# iterasi3.net
KiCad netlist of a schematic drawn in EAGLE
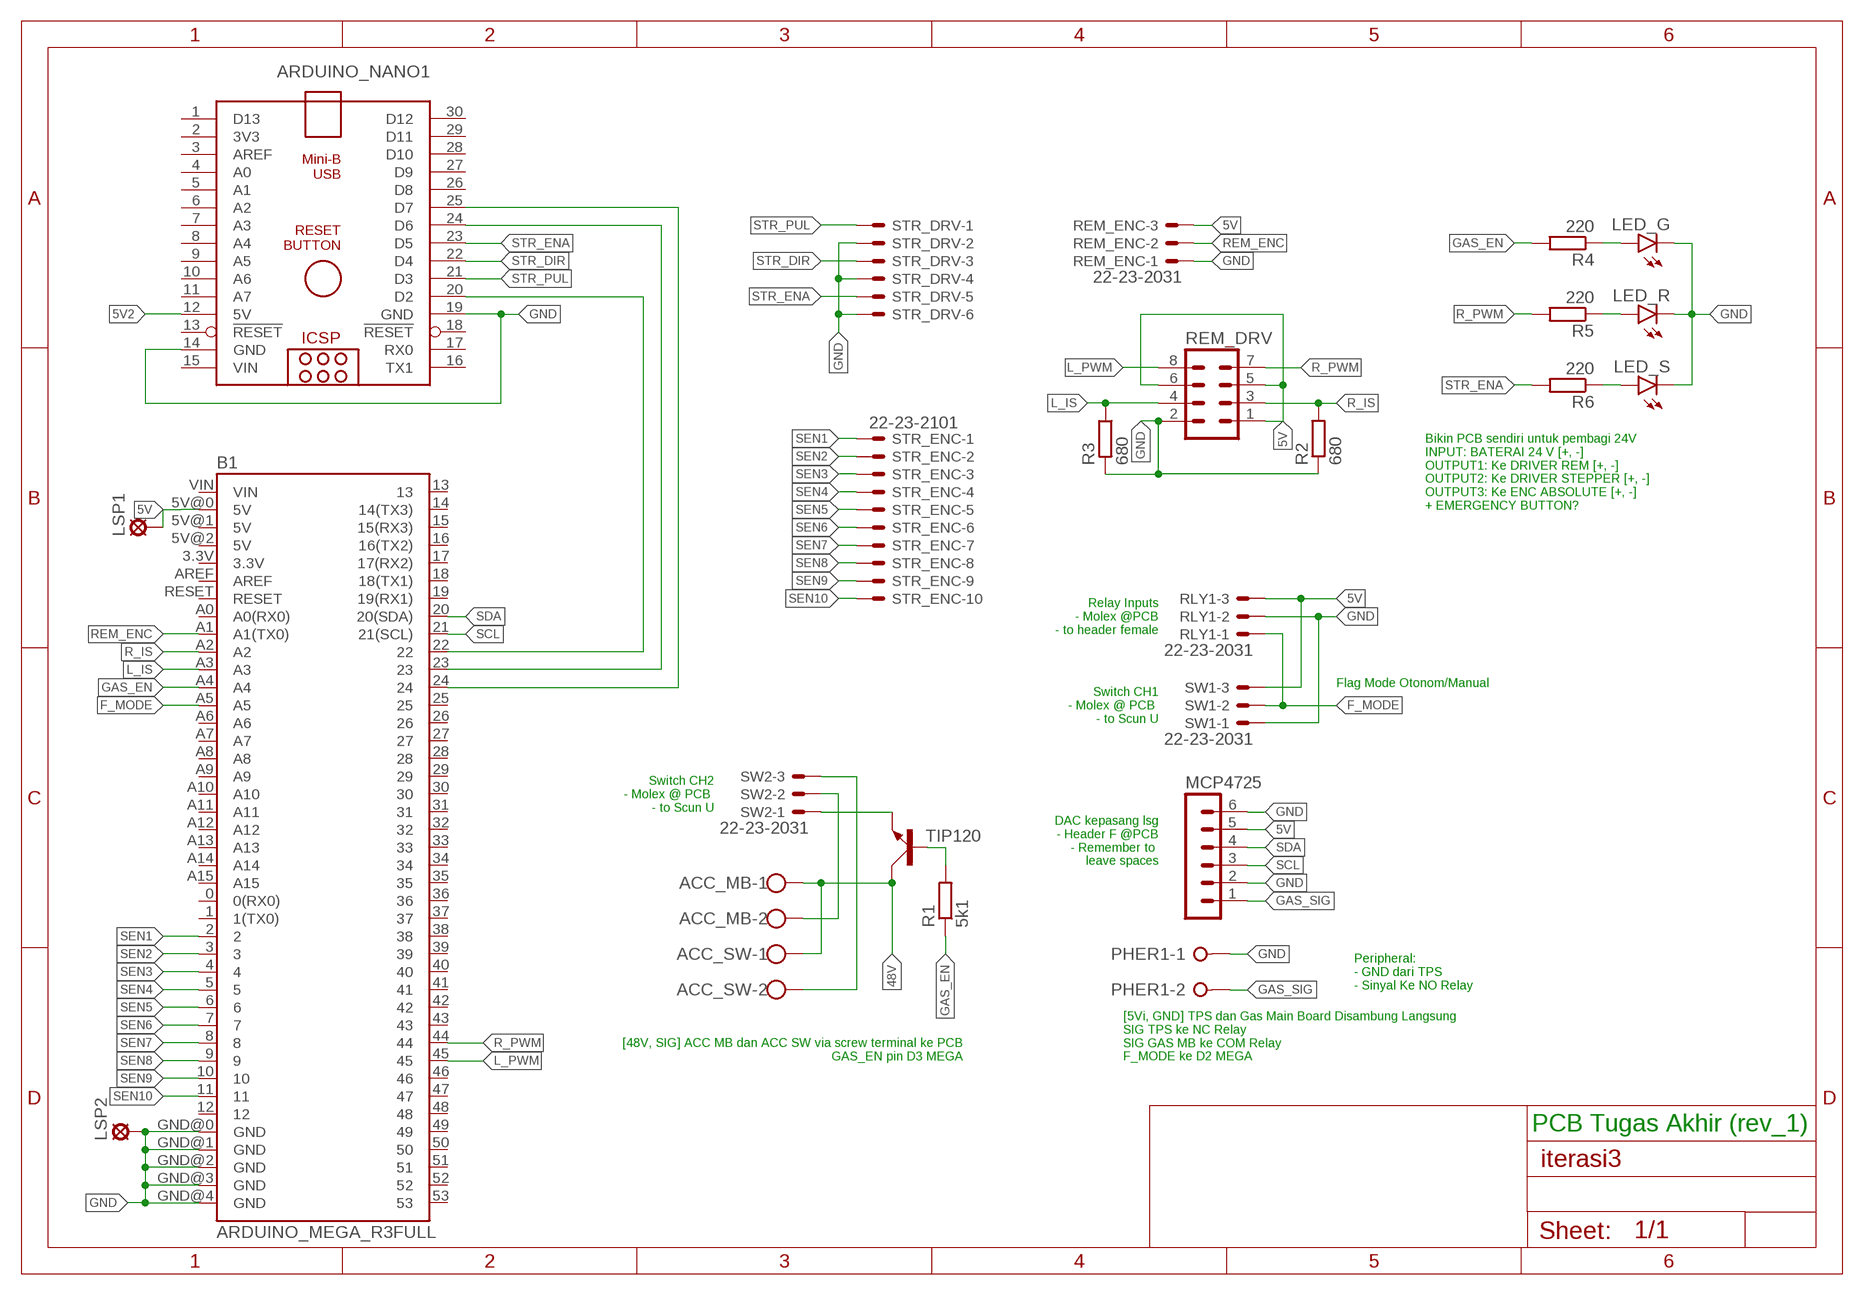
[diagram p0: schematic, sheet 1]

(export (version "E")
  (design (tool "Eeschema 10.0.6"))
  (components
    (comp (ref "ACC_MB")
      (value "W237-102")
      (footprint "eagle-import:W237-102")
      (fields (field (name "MPN") "237-102"))
      (libsource (lib "eagle-import") (part "W237-102"))
    )
    (comp (ref "ACC_SW")
      (value "W237-102")
      (footprint "eagle-import:W237-102")
      (fields (field (name "MPN") "237-102"))
      (libsource (lib "eagle-import") (part "W237-102"))
    )
    (comp (ref "ARDUINO_NANO1")
      (value "ARDUINO_NANO")
      (footprint "eagle-import:ARDUINO_NANO")
      (libsource (lib "eagle-import") (part "ARDUINO_NANO"))
    )
    (comp (ref "B1")
      (value "ARDUINO_MEGA_R3FULL")
      (footprint "eagle-import:ARDUINO_MEGA")
      (libsource (lib "eagle-import") (part "ARDUINO_MEGA_R3FULL"))
    )
    (comp (ref "LED_G")
      (value "TLLY4400")
      (footprint "eagle-import:LED3MM")
      (fields (field (name "MF") "VISHAY SEMICONDUCTOR"))
      (libsource (lib "eagle-import") (part "TLLY4400"))
    )
    (comp (ref "LED_R")
      (value "TLLY4400")
      (footprint "eagle-import:LED3MM")
      (fields (field (name "MF") "VISHAY SEMICONDUCTOR"))
      (libsource (lib "eagle-import") (part "TLLY4400"))
    )
    (comp (ref "LED_S")
      (value "TLLY4400")
      (footprint "eagle-import:LED3MM")
      (fields (field (name "MF") "VISHAY SEMICONDUCTOR"))
      (libsource (lib "eagle-import") (part "TLLY4400"))
    )
    (comp (ref "LSP1")
      (value "SE13")
      (footprint "eagle-import:SE13")
      (libsource (lib "eagle-import") (part "SE13"))
    )
    (comp (ref "LSP2")
      (value "SE13")
      (footprint "eagle-import:SE13")
      (libsource (lib "eagle-import") (part "SE13"))
    )
    (comp (ref "MCP4725")
      (value "MA06-1")
      (footprint "eagle-import:MA06-1")
      (libsource (lib "eagle-import") (part "MA06-1"))
    )
    (comp (ref "PHER1")
      (value "GND_TPS/RELAY_NO")
      (footprint "eagle-import:W237-132")
      (libsource (lib "eagle-import") (part "W237-02P"))
    )
    (comp (ref "R1")
      (value "5k1")
      (footprint "eagle-import:0207_10")
      (libsource (lib "eagle-import") (part "R-EU_0207/10"))
    )
    (comp (ref "R2")
      (value "680")
      (footprint "eagle-import:0207_10")
      (libsource (lib "eagle-import") (part "R-EU_0207/10"))
    )
    (comp (ref "R3")
      (value "680")
      (footprint "eagle-import:0207_10")
      (libsource (lib "eagle-import") (part "R-EU_0207/10"))
    )
    (comp (ref "R4")
      (value "220")
      (footprint "eagle-import:0207_10")
      (libsource (lib "eagle-import") (part "R-EU_0207/10"))
    )
    (comp (ref "R5")
      (value "220")
      (footprint "eagle-import:0207_10")
      (libsource (lib "eagle-import") (part "R-EU_0207/10"))
    )
    (comp (ref "R6")
      (value "220")
      (footprint "eagle-import:0207_10")
      (libsource (lib "eagle-import") (part "R-EU_0207/10"))
    )
    (comp (ref "REM_DRV")
      (value "MA04-2")
      (footprint "eagle-import:MA04-2")
      (libsource (lib "eagle-import") (part "MA04-2"))
    )
    (comp (ref "REM_ENC")
      (value "22-23-2031")
      (footprint "eagle-import:22-23-2031")
      (fields (field (name "MF") "MOLEX"))
      (libsource (lib "eagle-import") (part "22-23-2031"))
    )
    (comp (ref "RLY1")
      (value "22-23-2031")
      (footprint "eagle-import:22-23-2031")
      (fields (field (name "MF") "MOLEX"))
      (libsource (lib "eagle-import") (part "22-23-2031"))
    )
    (comp (ref "STR_DRV")
      (value "22-23-2061")
      (footprint "eagle-import:22-23-2061")
      (fields (field (name "MF") "MOLEX"))
      (libsource (lib "eagle-import") (part "22-23-2061"))
    )
    (comp (ref "STR_ENC")
      (value "22-23-2101")
      (footprint "eagle-import:22-23-2101")
      (fields (field (name "MF") "MOLEX"))
      (libsource (lib "eagle-import") (part "22-23-2101"))
    )
    (comp (ref "SW1")
      (value "22-23-2031")
      (footprint "eagle-import:22-23-2031")
      (fields (field (name "MF") "MOLEX"))
      (libsource (lib "eagle-import") (part "22-23-2031"))
    )
    (comp (ref "SW2")
      (value "22-23-2031")
      (footprint "eagle-import:22-23-2031")
      (fields (field (name "MF") "MOLEX"))
      (libsource (lib "eagle-import") (part "22-23-2031"))
    )
    (comp (ref "TIP120")
      (value "TIP41C")
      (footprint "eagle-import:TO220AV")
      (libsource (lib "eagle-import") (part "TIP41C"))
    )
  )
  (nets
    (net (code "1") (name "/VIN") (class "Default")
      (node (ref "ARDUINO_NANO1") (pin "15") (pinfunction "VIN_15") (pintype "power_in"))
    )
    (net (code "2") (name "5V") (class "Default")
      (node (ref "B1") (pin "5V@0") (pinfunction "5V_5V@0") (pintype "bidirectional"))
      (node (ref "LSP1") (pin "MP") (pinfunction "MP_MP") (pintype "passive"))
      (node (ref "MCP4725") (pin "5") (pinfunction "5_5") (pintype "passive"))
      (node (ref "REM_DRV") (pin "1") (pinfunction "1_1") (pintype "passive"))
      (node (ref "REM_DRV") (pin "5") (pinfunction "5_5") (pintype "passive"))
      (node (ref "REM_DRV") (pin "6") (pinfunction "6_6") (pintype "passive"))
      (node (ref "REM_ENC") (pin "3") (pinfunction "S_3") (pintype "passive"))
      (node (ref "RLY1") (pin "3") (pinfunction "S_3") (pintype "passive"))
      (node (ref "SW1") (pin "3") (pinfunction "S_3") (pintype "passive"))
    )
    (net (code "3") (name "5V2") (class "Default")
      (node (ref "ARDUINO_NANO1") (pin "12") (pinfunction "5V_12") (pintype "power_in"))
    )
    (net (code "4") (name "48V") (class "Default")
      (node (ref "ACC_MB") (pin "1") (pinfunction "KL_1") (pintype "passive"))
      (node (ref "ACC_SW") (pin "1") (pinfunction "KL_1") (pintype "passive"))
      (node (ref "TIP120") (pin "C") (pinfunction "C_C") (pintype "passive"))
    )
    (net (code "5") (name "F_MODE") (class "Default")
      (node (ref "B1") (pin "A5") (pinfunction "A5_A5") (pintype "bidirectional"))
      (node (ref "RLY1") (pin "1") (pinfunction "S_1") (pintype "passive"))
      (node (ref "SW1") (pin "2") (pinfunction "S_2") (pintype "passive"))
    )
    (net (code "6") (name "GAS_EN") (class "Default")
      (node (ref "B1") (pin "A4") (pinfunction "A4_A4") (pintype "bidirectional"))
      (node (ref "R1") (pin "1") (pinfunction "1_1") (pintype "passive"))
      (node (ref "R4") (pin "2") (pinfunction "2_2") (pintype "passive"))
    )
    (net (code "7") (name "GAS_SIG") (class "Default")
      (node (ref "MCP4725") (pin "1") (pinfunction "1_1") (pintype "passive"))
      (node (ref "PHER1") (pin "2") (pinfunction "KL_2") (pintype "passive"))
    )
    (net (code "8") (name "GND") (class "Default")
      (node (ref "ARDUINO_NANO1") (pin "14") (pinfunction "GND_14") (pintype "power_in"))
      (node (ref "ARDUINO_NANO1") (pin "19") (pinfunction "GND_19") (pintype "power_in"))
      (node (ref "B1") (pin "GND@0") (pinfunction "GND_GND@0") (pintype "bidirectional"))
      (node (ref "B1") (pin "GND@1") (pinfunction "GND_GND@1") (pintype "bidirectional"))
      (node (ref "B1") (pin "GND@2") (pinfunction "GND_GND@2") (pintype "bidirectional"))
      (node (ref "B1") (pin "GND@3") (pinfunction "GND_GND@3") (pintype "bidirectional"))
      (node (ref "B1") (pin "GND@4") (pinfunction "GND_GND@4") (pintype "bidirectional"))
      (node (ref "LED_G") (pin "K") (pinfunction "C_K") (pintype "passive"))
      (node (ref "LED_R") (pin "K") (pinfunction "C_K") (pintype "passive"))
      (node (ref "LED_S") (pin "K") (pinfunction "C_K") (pintype "passive"))
      (node (ref "LSP2") (pin "MP") (pinfunction "MP_MP") (pintype "passive"))
      (node (ref "MCP4725") (pin "2") (pinfunction "2_2") (pintype "passive"))
      (node (ref "MCP4725") (pin "6") (pinfunction "6_6") (pintype "passive"))
      (node (ref "PHER1") (pin "1") (pinfunction "KL_1") (pintype "passive"))
      (node (ref "R2") (pin "1") (pinfunction "1_1") (pintype "passive"))
      (node (ref "R3") (pin "2") (pinfunction "2_2") (pintype "passive"))
      (node (ref "REM_DRV") (pin "2") (pinfunction "2_2") (pintype "passive"))
      (node (ref "REM_ENC") (pin "1") (pinfunction "S_1") (pintype "passive"))
      (node (ref "RLY1") (pin "2") (pinfunction "S_2") (pintype "passive"))
      (node (ref "STR_DRV") (pin "2") (pinfunction "S_2") (pintype "passive"))
      (node (ref "STR_DRV") (pin "4") (pinfunction "S_4") (pintype "passive"))
      (node (ref "STR_DRV") (pin "6") (pinfunction "S_6") (pintype "passive"))
      (node (ref "SW1") (pin "1") (pinfunction "S_1") (pintype "passive"))
    )
    (net (code "9") (name "L_IS") (class "Default")
      (node (ref "B1") (pin "A3") (pinfunction "A3_A3") (pintype "bidirectional"))
      (node (ref "R3") (pin "1") (pinfunction "1_1") (pintype "passive"))
      (node (ref "REM_DRV") (pin "4") (pinfunction "4_4") (pintype "passive"))
    )
    (net (code "10") (name "L_PWM") (class "Default")
      (node (ref "B1") (pin "45") (pinfunction "45_45") (pintype "bidirectional"))
      (node (ref "REM_DRV") (pin "8") (pinfunction "8_8") (pintype "passive"))
    )
    (net (code "11") (name "Net-(ACC_MBB-KL)") (class "Default")
      (node (ref "ACC_MB") (pin "2") (pinfunction "KL_2") (pintype "passive"))
      (node (ref "SW2") (pin "2") (pinfunction "S_2") (pintype "passive"))
    )
    (net (code "12") (name "Net-(ACC_SWB-KL)") (class "Default")
      (node (ref "ACC_SW") (pin "2") (pinfunction "KL_2") (pintype "passive"))
      (node (ref "SW2") (pin "3") (pinfunction "S_3") (pintype "passive"))
    )
    (net (code "13") (name "Net-(ARDUINO_NANO1-D2)") (class "Default")
      (node (ref "ARDUINO_NANO1") (pin "20") (pinfunction "D2_20") (pintype "bidirectional"))
      (node (ref "B1") (pin "22") (pinfunction "22_22") (pintype "bidirectional"))
    )
    (net (code "14") (name "Net-(ARDUINO_NANO1-D6)") (class "Default")
      (node (ref "ARDUINO_NANO1") (pin "24") (pinfunction "D6_24") (pintype "bidirectional"))
      (node (ref "B1") (pin "23") (pinfunction "23_23") (pintype "bidirectional"))
    )
    (net (code "15") (name "Net-(ARDUINO_NANO1-D7)") (class "Default")
      (node (ref "ARDUINO_NANO1") (pin "25") (pinfunction "D7_25") (pintype "bidirectional"))
      (node (ref "B1") (pin "24") (pinfunction "24_24") (pintype "bidirectional"))
    )
    (net (code "16") (name "Net-(LED_G-PadA)") (class "Default")
      (node (ref "LED_G") (pin "A") (pinfunction "A_A") (pintype "passive"))
      (node (ref "R4") (pin "1") (pinfunction "1_1") (pintype "passive"))
    )
    (net (code "17") (name "Net-(LED_R-PadA)") (class "Default")
      (node (ref "LED_R") (pin "A") (pinfunction "A_A") (pintype "passive"))
      (node (ref "R5") (pin "1") (pinfunction "1_1") (pintype "passive"))
    )
    (net (code "18") (name "Net-(LED_S-PadA)") (class "Default")
      (node (ref "LED_S") (pin "A") (pinfunction "A_A") (pintype "passive"))
      (node (ref "R6") (pin "1") (pinfunction "1_1") (pintype "passive"))
    )
    (net (code "19") (name "Net-(R1-Pad2)") (class "Default")
      (node (ref "R1") (pin "2") (pinfunction "2_2") (pintype "passive"))
      (node (ref "TIP120") (pin "B") (pinfunction "B_B") (pintype "passive"))
    )
    (net (code "20") (name "Net-(SW2A-S)") (class "Default")
      (node (ref "SW2") (pin "1") (pinfunction "S_1") (pintype "passive"))
      (node (ref "TIP120") (pin "E") (pinfunction "E_E") (pintype "passive"))
    )
    (net (code "21") (name "REM_ENC") (class "Default")
      (node (ref "B1") (pin "A1") (pinfunction "A1(TX0)_A1") (pintype "bidirectional"))
      (node (ref "REM_ENC") (pin "2") (pinfunction "S_2") (pintype "passive"))
    )
    (net (code "22") (name "R_IS") (class "Default")
      (node (ref "B1") (pin "A2") (pinfunction "A2_A2") (pintype "bidirectional"))
      (node (ref "R2") (pin "2") (pinfunction "2_2") (pintype "passive"))
      (node (ref "REM_DRV") (pin "3") (pinfunction "3_3") (pintype "passive"))
    )
    (net (code "23") (name "R_PWM") (class "Default")
      (node (ref "B1") (pin "44") (pinfunction "44_44") (pintype "bidirectional"))
      (node (ref "R5") (pin "2") (pinfunction "2_2") (pintype "passive"))
      (node (ref "REM_DRV") (pin "7") (pinfunction "7_7") (pintype "passive"))
    )
    (net (code "24") (name "SCL") (class "Default")
      (node (ref "B1") (pin "21") (pinfunction "21(SCL)_21") (pintype "bidirectional"))
      (node (ref "MCP4725") (pin "3") (pinfunction "3_3") (pintype "passive"))
    )
    (net (code "25") (name "SDA") (class "Default")
      (node (ref "B1") (pin "20") (pinfunction "20(SDA)_20") (pintype "bidirectional"))
      (node (ref "MCP4725") (pin "4") (pinfunction "4_4") (pintype "passive"))
    )
    (net (code "26") (name "SEN1") (class "Default")
      (node (ref "B1") (pin "2") (pinfunction "2_2") (pintype "bidirectional"))
      (node (ref "STR_ENC") (pin "1") (pinfunction "S_1") (pintype "passive"))
    )
    (net (code "27") (name "SEN2") (class "Default")
      (node (ref "B1") (pin "3") (pinfunction "3_3") (pintype "bidirectional"))
      (node (ref "STR_ENC") (pin "2") (pinfunction "S_2") (pintype "passive"))
    )
    (net (code "28") (name "SEN3") (class "Default")
      (node (ref "B1") (pin "4") (pinfunction "4_4") (pintype "bidirectional"))
      (node (ref "STR_ENC") (pin "3") (pinfunction "S_3") (pintype "passive"))
    )
    (net (code "29") (name "SEN4") (class "Default")
      (node (ref "B1") (pin "5") (pinfunction "5_5") (pintype "bidirectional"))
      (node (ref "STR_ENC") (pin "4") (pinfunction "S_4") (pintype "passive"))
    )
    (net (code "30") (name "SEN5") (class "Default")
      (node (ref "B1") (pin "6") (pinfunction "6_6") (pintype "bidirectional"))
      (node (ref "STR_ENC") (pin "5") (pinfunction "S_5") (pintype "passive"))
    )
    (net (code "31") (name "SEN6") (class "Default")
      (node (ref "B1") (pin "7") (pinfunction "7_7") (pintype "bidirectional"))
      (node (ref "STR_ENC") (pin "6") (pinfunction "S_6") (pintype "passive"))
    )
    (net (code "32") (name "SEN7") (class "Default")
      (node (ref "B1") (pin "8") (pinfunction "8_8") (pintype "bidirectional"))
      (node (ref "STR_ENC") (pin "7") (pinfunction "S_7") (pintype "passive"))
    )
    (net (code "33") (name "SEN8") (class "Default")
      (node (ref "B1") (pin "9") (pinfunction "9_9") (pintype "bidirectional"))
      (node (ref "STR_ENC") (pin "8") (pinfunction "S_8") (pintype "passive"))
    )
    (net (code "34") (name "SEN9") (class "Default")
      (node (ref "B1") (pin "10") (pinfunction "10_10") (pintype "bidirectional"))
      (node (ref "STR_ENC") (pin "9") (pinfunction "S_9") (pintype "passive"))
    )
    (net (code "35") (name "SEN10") (class "Default")
      (node (ref "B1") (pin "11") (pinfunction "11_11") (pintype "bidirectional"))
      (node (ref "STR_ENC") (pin "10") (pinfunction "S_10") (pintype "passive"))
    )
    (net (code "36") (name "STR_DIR") (class "Default")
      (node (ref "ARDUINO_NANO1") (pin "22") (pinfunction "D4_22") (pintype "bidirectional"))
      (node (ref "STR_DRV") (pin "3") (pinfunction "S_3") (pintype "passive"))
    )
    (net (code "37") (name "STR_ENA") (class "Default")
      (node (ref "ARDUINO_NANO1") (pin "23") (pinfunction "D5_23") (pintype "bidirectional"))
      (node (ref "R6") (pin "2") (pinfunction "2_2") (pintype "passive"))
      (node (ref "STR_DRV") (pin "5") (pinfunction "S_5") (pintype "passive"))
    )
    (net (code "38") (name "STR_PUL") (class "Default")
      (node (ref "ARDUINO_NANO1") (pin "21") (pinfunction "D3_21") (pintype "bidirectional"))
      (node (ref "STR_DRV") (pin "1") (pinfunction "S_1") (pintype "passive"))
    )
    (net (code "39") (name "unconnected-(ARDUINO_NANO1-3V3-Pad2)") (class "Default")
      (node (ref "ARDUINO_NANO1") (pin "2") (pinfunction "3V3_2") (pintype "output"))
    )
    (net (code "40") (name "unconnected-(ARDUINO_NANO1-A0-Pad4)") (class "Default")
      (node (ref "ARDUINO_NANO1") (pin "4") (pinfunction "A0_4") (pintype "bidirectional"))
    )
    (net (code "41") (name "unconnected-(ARDUINO_NANO1-A1-Pad5)") (class "Default")
      (node (ref "ARDUINO_NANO1") (pin "5") (pinfunction "A1_5") (pintype "bidirectional"))
    )
    (net (code "42") (name "unconnected-(ARDUINO_NANO1-A2-Pad6)") (class "Default")
      (node (ref "ARDUINO_NANO1") (pin "6") (pinfunction "A2_6") (pintype "bidirectional"))
    )
    (net (code "43") (name "unconnected-(ARDUINO_NANO1-A3-Pad7)") (class "Default")
      (node (ref "ARDUINO_NANO1") (pin "7") (pinfunction "A3_7") (pintype "bidirectional"))
    )
    (net (code "44") (name "unconnected-(ARDUINO_NANO1-A4-Pad8)") (class "Default")
      (node (ref "ARDUINO_NANO1") (pin "8") (pinfunction "A4_8") (pintype "bidirectional"))
    )
    (net (code "45") (name "unconnected-(ARDUINO_NANO1-A5-Pad9)") (class "Default")
      (node (ref "ARDUINO_NANO1") (pin "9") (pinfunction "A5_9") (pintype "bidirectional"))
    )
    (net (code "46") (name "unconnected-(ARDUINO_NANO1-A6-Pad10)") (class "Default")
      (node (ref "ARDUINO_NANO1") (pin "10") (pinfunction "A6_10") (pintype "bidirectional"))
    )
    (net (code "47") (name "unconnected-(ARDUINO_NANO1-A7-Pad11)") (class "Default")
      (node (ref "ARDUINO_NANO1") (pin "11") (pinfunction "A7_11") (pintype "bidirectional"))
    )
    (net (code "48") (name "unconnected-(ARDUINO_NANO1-AREF-Pad3)") (class "Default")
      (node (ref "ARDUINO_NANO1") (pin "3") (pinfunction "AREF_3") (pintype "input"))
    )
    (net (code "49") (name "unconnected-(ARDUINO_NANO1-D8-Pad26)") (class "Default")
      (node (ref "ARDUINO_NANO1") (pin "26") (pinfunction "D8_26") (pintype "bidirectional"))
    )
    (net (code "50") (name "unconnected-(ARDUINO_NANO1-D9-Pad27)") (class "Default")
      (node (ref "ARDUINO_NANO1") (pin "27") (pinfunction "D9_27") (pintype "bidirectional"))
    )
    (net (code "51") (name "unconnected-(ARDUINO_NANO1-D10-Pad28)") (class "Default")
      (node (ref "ARDUINO_NANO1") (pin "28") (pinfunction "D10_28") (pintype "bidirectional"))
    )
    (net (code "52") (name "unconnected-(ARDUINO_NANO1-D11-Pad29)") (class "Default")
      (node (ref "ARDUINO_NANO1") (pin "29") (pinfunction "D11_29") (pintype "bidirectional"))
    )
    (net (code "53") (name "unconnected-(ARDUINO_NANO1-D12-Pad30)") (class "Default")
      (node (ref "ARDUINO_NANO1") (pin "30") (pinfunction "D12_30") (pintype "bidirectional"))
    )
    (net (code "54") (name "unconnected-(ARDUINO_NANO1-D13-Pad1)") (class "Default")
      (node (ref "ARDUINO_NANO1") (pin "1") (pinfunction "D13_1") (pintype "bidirectional"))
    )
    (net (code "55") (name "unconnected-(ARDUINO_NANO1-RX0-Pad17)") (class "Default")
      (node (ref "ARDUINO_NANO1") (pin "17") (pinfunction "RX0_17") (pintype "bidirectional"))
    )
    (net (code "56") (name "unconnected-(ARDUINO_NANO1-TX1-Pad16)") (class "Default")
      (node (ref "ARDUINO_NANO1") (pin "16") (pinfunction "TX1_16") (pintype "bidirectional"))
    )
    (net (code "57") (name "unconnected-(ARDUINO_NANO1-~{RESET}-Pad13)") (class "Default")
      (node (ref "ARDUINO_NANO1") (pin "13") (pinfunction "~{RESET}_13") (pintype "input"))
    )
    (net (code "58") (name "unconnected-(ARDUINO_NANO1-~{RESET}-Pad18)") (class "Default")
      (node (ref "ARDUINO_NANO1") (pin "18") (pinfunction "~{RESET}_18") (pintype "input"))
    )
    (net (code "59") (name "unconnected-(B1-0(RX0)-Pad0)") (class "Default")
      (node (ref "B1") (pin "0") (pinfunction "0(RX0)_0") (pintype "bidirectional"))
    )
    (net (code "60") (name "unconnected-(B1-1(TX0)-Pad1)") (class "Default")
      (node (ref "B1") (pin "1") (pinfunction "1(TX0)_1") (pintype "bidirectional"))
    )
    (net (code "61") (name "unconnected-(B1-5V-Pad5V@1)") (class "Default")
      (node (ref "B1") (pin "5V@1") (pinfunction "5V_5V@1") (pintype "bidirectional"))
    )
    (net (code "62") (name "unconnected-(B1-5V-Pad5V@2)") (class "Default")
      (node (ref "B1") (pin "5V@2") (pinfunction "5V_5V@2") (pintype "bidirectional"))
    )
    (net (code "63") (name "unconnected-(B1-14(TX3)-Pad14)") (class "Default")
      (node (ref "B1") (pin "14") (pinfunction "14(TX3)_14") (pintype "bidirectional"))
    )
    (net (code "64") (name "unconnected-(B1-15(RX3)-Pad15)") (class "Default")
      (node (ref "B1") (pin "15") (pinfunction "15(RX3)_15") (pintype "bidirectional"))
    )
    (net (code "65") (name "unconnected-(B1-16(TX2)-Pad16)") (class "Default")
      (node (ref "B1") (pin "16") (pinfunction "16(TX2)_16") (pintype "bidirectional"))
    )
    (net (code "66") (name "unconnected-(B1-17(RX2)-Pad17)") (class "Default")
      (node (ref "B1") (pin "17") (pinfunction "17(RX2)_17") (pintype "bidirectional"))
    )
    (net (code "67") (name "unconnected-(B1-18(TX1)-Pad18)") (class "Default")
      (node (ref "B1") (pin "18") (pinfunction "18(TX1)_18") (pintype "bidirectional"))
    )
    (net (code "68") (name "unconnected-(B1-19(RX1)-Pad19)") (class "Default")
      (node (ref "B1") (pin "19") (pinfunction "19(RX1)_19") (pintype "bidirectional"))
    )
    (net (code "69") (name "unconnected-(B1-A0(RX0)-PadA0)") (class "Default")
      (node (ref "B1") (pin "A0") (pinfunction "A0(RX0)_A0") (pintype "bidirectional"))
    )
    (net (code "70") (name "unconnected-(B1-Pad3.3V)") (class "Default")
      (node (ref "B1") (pin "3.3V") (pinfunction "3.3V_3.3V") (pintype "bidirectional"))
    )
    (net (code "71") (name "unconnected-(B1-Pad12)") (class "Default")
      (node (ref "B1") (pin "12") (pinfunction "12_12") (pintype "bidirectional"))
    )
    (net (code "72") (name "unconnected-(B1-Pad13)") (class "Default")
      (node (ref "B1") (pin "13") (pinfunction "13_13") (pintype "bidirectional"))
    )
    (net (code "73") (name "unconnected-(B1-Pad25)") (class "Default")
      (node (ref "B1") (pin "25") (pinfunction "25_25") (pintype "bidirectional"))
    )
    (net (code "74") (name "unconnected-(B1-Pad26)") (class "Default")
      (node (ref "B1") (pin "26") (pinfunction "26_26") (pintype "bidirectional"))
    )
    (net (code "75") (name "unconnected-(B1-Pad27)") (class "Default")
      (node (ref "B1") (pin "27") (pinfunction "27_27") (pintype "bidirectional"))
    )
    (net (code "76") (name "unconnected-(B1-Pad28)") (class "Default")
      (node (ref "B1") (pin "28") (pinfunction "28_28") (pintype "bidirectional"))
    )
    (net (code "77") (name "unconnected-(B1-Pad29)") (class "Default")
      (node (ref "B1") (pin "29") (pinfunction "29_29") (pintype "bidirectional"))
    )
    (net (code "78") (name "unconnected-(B1-Pad30)") (class "Default")
      (node (ref "B1") (pin "30") (pinfunction "30_30") (pintype "bidirectional"))
    )
    (net (code "79") (name "unconnected-(B1-Pad31)") (class "Default")
      (node (ref "B1") (pin "31") (pinfunction "31_31") (pintype "bidirectional"))
    )
    (net (code "80") (name "unconnected-(B1-Pad32)") (class "Default")
      (node (ref "B1") (pin "32") (pinfunction "32_32") (pintype "bidirectional"))
    )
    (net (code "81") (name "unconnected-(B1-Pad33)") (class "Default")
      (node (ref "B1") (pin "33") (pinfunction "33_33") (pintype "bidirectional"))
    )
    (net (code "82") (name "unconnected-(B1-Pad34)") (class "Default")
      (node (ref "B1") (pin "34") (pinfunction "34_34") (pintype "bidirectional"))
    )
    (net (code "83") (name "unconnected-(B1-Pad35)") (class "Default")
      (node (ref "B1") (pin "35") (pinfunction "35_35") (pintype "bidirectional"))
    )
    (net (code "84") (name "unconnected-(B1-Pad36)") (class "Default")
      (node (ref "B1") (pin "36") (pinfunction "36_36") (pintype "bidirectional"))
    )
    (net (code "85") (name "unconnected-(B1-Pad37)") (class "Default")
      (node (ref "B1") (pin "37") (pinfunction "37_37") (pintype "bidirectional"))
    )
    (net (code "86") (name "unconnected-(B1-Pad38)") (class "Default")
      (node (ref "B1") (pin "38") (pinfunction "38_38") (pintype "bidirectional"))
    )
    (net (code "87") (name "unconnected-(B1-Pad39)") (class "Default")
      (node (ref "B1") (pin "39") (pinfunction "39_39") (pintype "bidirectional"))
    )
    (net (code "88") (name "unconnected-(B1-Pad40)") (class "Default")
      (node (ref "B1") (pin "40") (pinfunction "40_40") (pintype "bidirectional"))
    )
    (net (code "89") (name "unconnected-(B1-Pad41)") (class "Default")
      (node (ref "B1") (pin "41") (pinfunction "41_41") (pintype "bidirectional"))
    )
    (net (code "90") (name "unconnected-(B1-Pad42)") (class "Default")
      (node (ref "B1") (pin "42") (pinfunction "42_42") (pintype "bidirectional"))
    )
    (net (code "91") (name "unconnected-(B1-Pad43)") (class "Default")
      (node (ref "B1") (pin "43") (pinfunction "43_43") (pintype "bidirectional"))
    )
    (net (code "92") (name "unconnected-(B1-Pad46)") (class "Default")
      (node (ref "B1") (pin "46") (pinfunction "46_46") (pintype "bidirectional"))
    )
    (net (code "93") (name "unconnected-(B1-Pad47)") (class "Default")
      (node (ref "B1") (pin "47") (pinfunction "47_47") (pintype "bidirectional"))
    )
    (net (code "94") (name "unconnected-(B1-Pad48)") (class "Default")
      (node (ref "B1") (pin "48") (pinfunction "48_48") (pintype "bidirectional"))
    )
    (net (code "95") (name "unconnected-(B1-Pad49)") (class "Default")
      (node (ref "B1") (pin "49") (pinfunction "49_49") (pintype "bidirectional"))
    )
    (net (code "96") (name "unconnected-(B1-Pad50)") (class "Default")
      (node (ref "B1") (pin "50") (pinfunction "50_50") (pintype "bidirectional"))
    )
    (net (code "97") (name "unconnected-(B1-Pad51)") (class "Default")
      (node (ref "B1") (pin "51") (pinfunction "51_51") (pintype "bidirectional"))
    )
    (net (code "98") (name "unconnected-(B1-Pad52)") (class "Default")
      (node (ref "B1") (pin "52") (pinfunction "52_52") (pintype "bidirectional"))
    )
    (net (code "99") (name "unconnected-(B1-Pad53)") (class "Default")
      (node (ref "B1") (pin "53") (pinfunction "53_53") (pintype "bidirectional"))
    )
    (net (code "100") (name "unconnected-(B1-PadA6)") (class "Default")
      (node (ref "B1") (pin "A6") (pinfunction "A6_A6") (pintype "bidirectional"))
    )
    (net (code "101") (name "unconnected-(B1-PadA7)") (class "Default")
      (node (ref "B1") (pin "A7") (pinfunction "A7_A7") (pintype "bidirectional"))
    )
    (net (code "102") (name "unconnected-(B1-PadA8)") (class "Default")
      (node (ref "B1") (pin "A8") (pinfunction "A8_A8") (pintype "bidirectional"))
    )
    (net (code "103") (name "unconnected-(B1-PadA9)") (class "Default")
      (node (ref "B1") (pin "A9") (pinfunction "A9_A9") (pintype "bidirectional"))
    )
    (net (code "104") (name "unconnected-(B1-PadA10)") (class "Default")
      (node (ref "B1") (pin "A10") (pinfunction "A10_A10") (pintype "bidirectional"))
    )
    (net (code "105") (name "unconnected-(B1-PadA11)") (class "Default")
      (node (ref "B1") (pin "A11") (pinfunction "A11_A11") (pintype "bidirectional"))
    )
    (net (code "106") (name "unconnected-(B1-PadA12)") (class "Default")
      (node (ref "B1") (pin "A12") (pinfunction "A12_A12") (pintype "bidirectional"))
    )
    (net (code "107") (name "unconnected-(B1-PadA13)") (class "Default")
      (node (ref "B1") (pin "A13") (pinfunction "A13_A13") (pintype "bidirectional"))
    )
    (net (code "108") (name "unconnected-(B1-PadA14)") (class "Default")
      (node (ref "B1") (pin "A14") (pinfunction "A14_A14") (pintype "bidirectional"))
    )
    (net (code "109") (name "unconnected-(B1-PadA15)") (class "Default")
      (node (ref "B1") (pin "A15") (pinfunction "A15_A15") (pintype "bidirectional"))
    )
    (net (code "110") (name "unconnected-(B1-PadAREF)") (class "Default")
      (node (ref "B1") (pin "AREF") (pinfunction "AREF_AREF") (pintype "bidirectional"))
    )
    (net (code "111") (name "unconnected-(B1-PadRESET)") (class "Default")
      (node (ref "B1") (pin "RESET") (pinfunction "RESET_RESET") (pintype "bidirectional"))
    )
    (net (code "112") (name "unconnected-(B1-PadVIN)") (class "Default")
      (node (ref "B1") (pin "VIN") (pinfunction "VIN_VIN") (pintype "bidirectional"))
    )
  )
)
